# 11-UWB-Main.net
KiCad netlist of a schematic drawn in Altium Designer
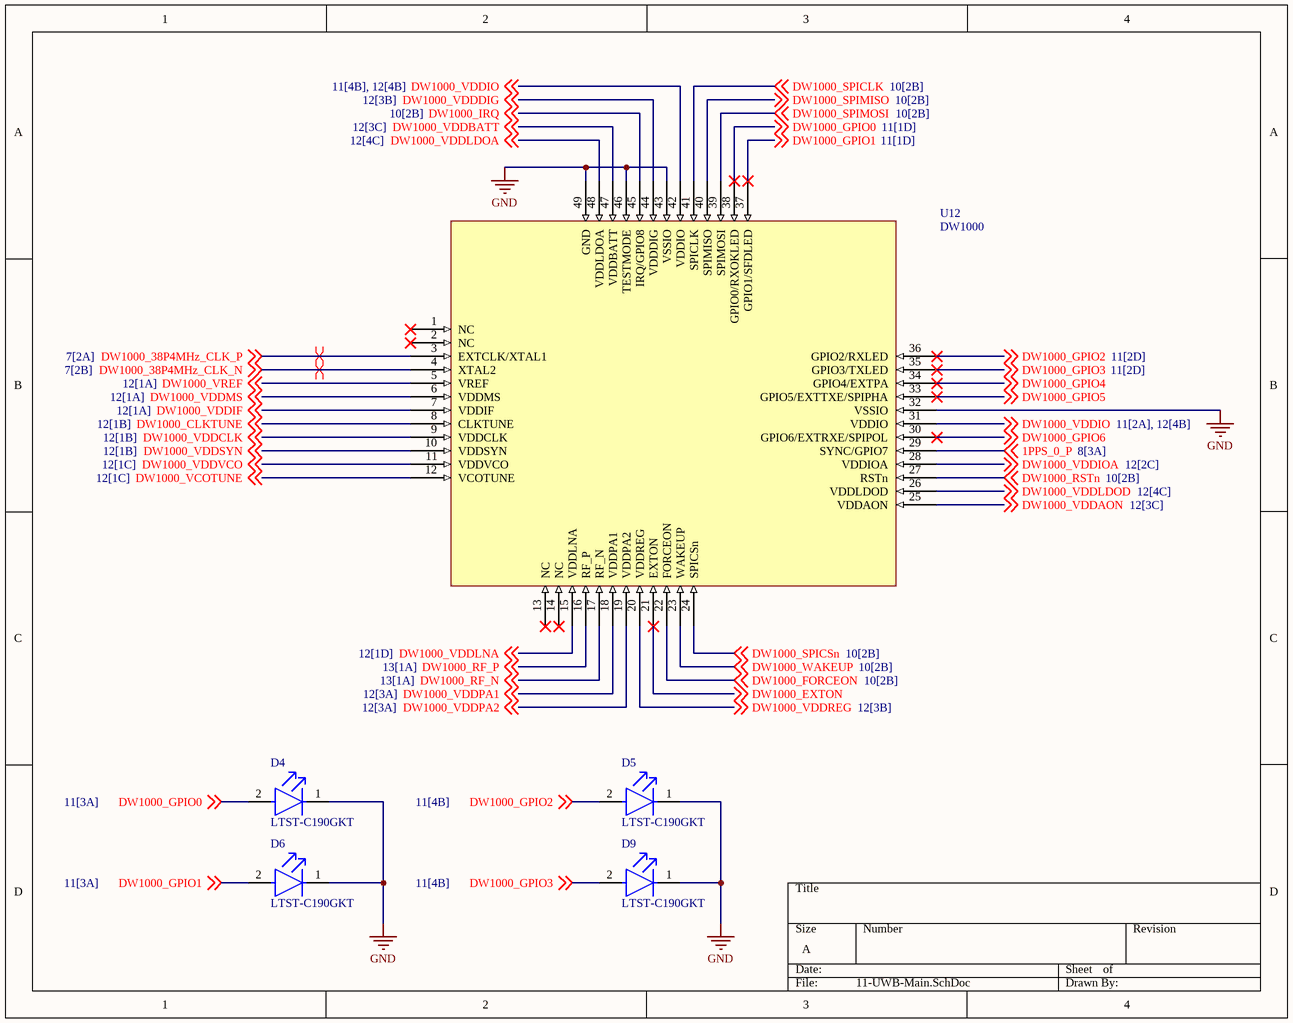
[diagram p0: 11-UWB-Main.SchDoc]

(export (version "E")
  (design (tool "Eeschema 10.0.6"))
  (components
    (comp (ref "D4")
      (value "LTST-C190GKT")
      (footprint "FP-LTST-C190GKT-MFG")
      (description "LED GREEN CLEAR CHIP SMD")
      (fields (field (name "VOLTAGE") "2V"))
      (libsource (lib "Altium Content Vault") (part "8706943c75ba83719d021d2fdc84c58"))
    )
    (comp (ref "D5")
      (value "LTST-C190GKT")
      (footprint "FP-LTST-C190GKT-MFG")
      (description "LED GREEN CLEAR CHIP SMD")
      (fields (field (name "VOLTAGE") "2V"))
      (libsource (lib "Altium Content Vault") (part "8706943c75ba83719d021d2fdc84c58"))
    )
    (comp (ref "D6")
      (value "LTST-C190GKT")
      (footprint "FP-LTST-C190GKT-MFG")
      (description "LED GREEN CLEAR CHIP SMD")
      (fields (field (name "VOLTAGE") "2V"))
      (libsource (lib "Altium Content Vault") (part "8706943c75ba83719d021d2fdc84c58"))
    )
    (comp (ref "D9")
      (value "LTST-C190GKT")
      (footprint "FP-LTST-C190GKT-MFG")
      (description "LED GREEN CLEAR CHIP SMD")
      (fields (field (name "VOLTAGE") "2V"))
      (libsource (lib "Altium Content Vault") (part "8706943c75ba83719d021d2fdc84c58"))
    )
    (comp (ref "U12")
      (value "DW1000")
      (footprint "QFN40P600X600X90-49N-D")
      (libsource (lib "TimeDrive_Lib") (part "DW1000"))
    )
  )
  (nets
    (net (code "1") (name "1PPS_0_P") (class "Default")
      (node (ref "U12") (pin "29") (pinfunction "SYNC/GPIO7_29") (pintype "input"))
    )
    (net (code "2") (name "DW1000_38P4MHz_CLK_N") (class "Default")
      (node (ref "U12") (pin "4") (pinfunction "XTAL2_4") (pintype "input"))
    )
    (net (code "3") (name "DW1000_38P4MHz_CLK_P") (class "Default")
      (node (ref "U12") (pin "3") (pinfunction "EXTCLK/XTAL1_3") (pintype "input"))
    )
    (net (code "4") (name "DW1000_CLKTUNE") (class "Default")
      (node (ref "U12") (pin "8") (pinfunction "CLKTUNE_8") (pintype "input"))
    )
    (net (code "5") (name "DW1000_EXTON") (class "Default")
      (node (ref "U12") (pin "21") (pinfunction "EXTON_21") (pintype "input"))
    )
    (net (code "6") (name "DW1000_FORCEON") (class "Default")
      (node (ref "U12") (pin "22") (pinfunction "FORCEON_22") (pintype "input"))
    )
    (net (code "7") (name "DW1000_GPIO0") (class "Default")
      (node (ref "D4") (pin "2") (pinfunction "A_2") (pintype "passive"))
      (node (ref "U12") (pin "38") (pinfunction "GPIO0/RXOKLED_38") (pintype "input"))
    )
    (net (code "8") (name "DW1000_GPIO1") (class "Default")
      (node (ref "D6") (pin "2") (pinfunction "A_2") (pintype "passive"))
      (node (ref "U12") (pin "37") (pinfunction "GPIO1/SFDLED_37") (pintype "input"))
    )
    (net (code "9") (name "DW1000_GPIO2") (class "Default")
      (node (ref "D5") (pin "2") (pinfunction "A_2") (pintype "passive"))
      (node (ref "U12") (pin "36") (pinfunction "GPIO2/RXLED_36") (pintype "input"))
    )
    (net (code "10") (name "DW1000_GPIO3") (class "Default")
      (node (ref "D9") (pin "2") (pinfunction "A_2") (pintype "passive"))
      (node (ref "U12") (pin "35") (pinfunction "GPIO3/TXLED_35") (pintype "input"))
    )
    (net (code "11") (name "DW1000_GPIO4") (class "Default")
      (node (ref "U12") (pin "34") (pinfunction "GPIO4/EXTPA_34") (pintype "input"))
    )
    (net (code "12") (name "DW1000_GPIO5") (class "Default")
      (node (ref "U12") (pin "33") (pinfunction "GPIO5/EXTTXE/SPIPHA_33") (pintype "input"))
    )
    (net (code "13") (name "DW1000_GPIO6") (class "Default")
      (node (ref "U12") (pin "30") (pinfunction "GPIO6/EXTRXE/SPIPOL_30") (pintype "input"))
    )
    (net (code "14") (name "DW1000_IRQ") (class "Default")
      (node (ref "U12") (pin "45") (pinfunction "IRQ/GPIO8_45") (pintype "input"))
    )
    (net (code "15") (name "DW1000_RF_N") (class "Default")
      (node (ref "U12") (pin "17") (pinfunction "RF_N_17") (pintype "input"))
    )
    (net (code "16") (name "DW1000_RF_P") (class "Default")
      (node (ref "U12") (pin "16") (pinfunction "RF_P_16") (pintype "input"))
    )
    (net (code "17") (name "DW1000_RSTn") (class "Default")
      (node (ref "U12") (pin "27") (pinfunction "RSTn_27") (pintype "input"))
    )
    (net (code "18") (name "DW1000_SPICLK") (class "Default")
      (node (ref "U12") (pin "41") (pinfunction "SPICLK_41") (pintype "input"))
    )
    (net (code "19") (name "DW1000_SPICSn") (class "Default")
      (node (ref "U12") (pin "24") (pinfunction "SPICSn_24") (pintype "input"))
    )
    (net (code "20") (name "DW1000_SPIMISO") (class "Default")
      (node (ref "U12") (pin "40") (pinfunction "SPIMISO_40") (pintype "input"))
    )
    (net (code "21") (name "DW1000_SPIMOSI") (class "Default")
      (node (ref "U12") (pin "39") (pinfunction "SPIMOSI_39") (pintype "input"))
    )
    (net (code "22") (name "DW1000_VCOTUNE") (class "Default")
      (node (ref "U12") (pin "12") (pinfunction "VCOTUNE_12") (pintype "input"))
    )
    (net (code "23") (name "DW1000_VDDAON") (class "Default")
      (node (ref "U12") (pin "25") (pinfunction "VDDAON_25") (pintype "input"))
    )
    (net (code "24") (name "DW1000_VDDBATT") (class "Default")
      (node (ref "U12") (pin "47") (pinfunction "VDDBATT_47") (pintype "input"))
    )
    (net (code "25") (name "DW1000_VDDCLK") (class "Default")
      (node (ref "U12") (pin "9") (pinfunction "VDDCLK_9") (pintype "input"))
    )
    (net (code "26") (name "DW1000_VDDDIG") (class "Default")
      (node (ref "U12") (pin "44") (pinfunction "VDDDIG_44") (pintype "input"))
    )
    (net (code "27") (name "DW1000_VDDIF") (class "Default")
      (node (ref "U12") (pin "7") (pinfunction "VDDIF_7") (pintype "input"))
    )
    (net (code "28") (name "DW1000_VDDIO") (class "Default")
      (node (ref "U12") (pin "31") (pinfunction "VDDIO_31") (pintype "input"))
      (node (ref "U12") (pin "42") (pinfunction "VDDIO_42") (pintype "input"))
    )
    (net (code "29") (name "DW1000_VDDIOA") (class "Default")
      (node (ref "U12") (pin "28") (pinfunction "VDDIOA_28") (pintype "input"))
    )
    (net (code "30") (name "DW1000_VDDLDOA") (class "Default")
      (node (ref "U12") (pin "48") (pinfunction "VDDLDOA_48") (pintype "input"))
    )
    (net (code "31") (name "DW1000_VDDLDOD") (class "Default")
      (node (ref "U12") (pin "26") (pinfunction "VDDLDOD_26") (pintype "input"))
    )
    (net (code "32") (name "DW1000_VDDLNA") (class "Default")
      (node (ref "U12") (pin "15") (pinfunction "VDDLNA_15") (pintype "input"))
    )
    (net (code "33") (name "DW1000_VDDMS") (class "Default")
      (node (ref "U12") (pin "6") (pinfunction "VDDMS_6") (pintype "input"))
    )
    (net (code "34") (name "DW1000_VDDPA1") (class "Default")
      (node (ref "U12") (pin "18") (pinfunction "VDDPA1_18") (pintype "input"))
    )
    (net (code "35") (name "DW1000_VDDPA2") (class "Default")
      (node (ref "U12") (pin "19") (pinfunction "VDDPA2_19") (pintype "input"))
    )
    (net (code "36") (name "DW1000_VDDREG") (class "Default")
      (node (ref "U12") (pin "20") (pinfunction "VDDREG_20") (pintype "input"))
    )
    (net (code "37") (name "DW1000_VDDSYN") (class "Default")
      (node (ref "U12") (pin "10") (pinfunction "VDDSYN_10") (pintype "input"))
    )
    (net (code "38") (name "DW1000_VDDVCO") (class "Default")
      (node (ref "U12") (pin "11") (pinfunction "VDDVCO_11") (pintype "input"))
    )
    (net (code "39") (name "DW1000_VREF") (class "Default")
      (node (ref "U12") (pin "5") (pinfunction "VREF_5") (pintype "input"))
    )
    (net (code "40") (name "DW1000_WAKEUP") (class "Default")
      (node (ref "U12") (pin "23") (pinfunction "WAKEUP_23") (pintype "input"))
    )
    (net (code "41") (name "GND") (class "Default")
      (node (ref "D4") (pin "1") (pinfunction "C_1") (pintype "passive"))
      (node (ref "D5") (pin "1") (pinfunction "C_1") (pintype "passive"))
      (node (ref "D6") (pin "1") (pinfunction "C_1") (pintype "passive"))
      (node (ref "D9") (pin "1") (pinfunction "C_1") (pintype "passive"))
      (node (ref "U12") (pin "32") (pinfunction "VSSIO_32") (pintype "input"))
      (node (ref "U12") (pin "43") (pinfunction "VSSIO_43") (pintype "input"))
      (node (ref "U12") (pin "46") (pinfunction "TESTMODE_46") (pintype "input"))
      (node (ref "U12") (pin "49") (pinfunction "GND_49") (pintype "input"))
    )
    (net (code "42") (name "unconnected-(U12-NC-Pad1)") (class "Default")
      (node (ref "U12") (pin "1") (pinfunction "NC_1") (pintype "input+no_connect"))
    )
    (net (code "43") (name "unconnected-(U12-NC-Pad2)") (class "Default")
      (node (ref "U12") (pin "2") (pinfunction "NC_2") (pintype "input+no_connect"))
    )
    (net (code "44") (name "unconnected-(U12-NC-Pad13)") (class "Default")
      (node (ref "U12") (pin "13") (pinfunction "NC_13") (pintype "input+no_connect"))
    )
    (net (code "45") (name "unconnected-(U12-NC-Pad14)") (class "Default")
      (node (ref "U12") (pin "14") (pinfunction "NC_14") (pintype "input+no_connect"))
    )
  )
)
